# Signal_Generator_SCH.net
KiCad netlist of a schematic drawn in Altium Designer
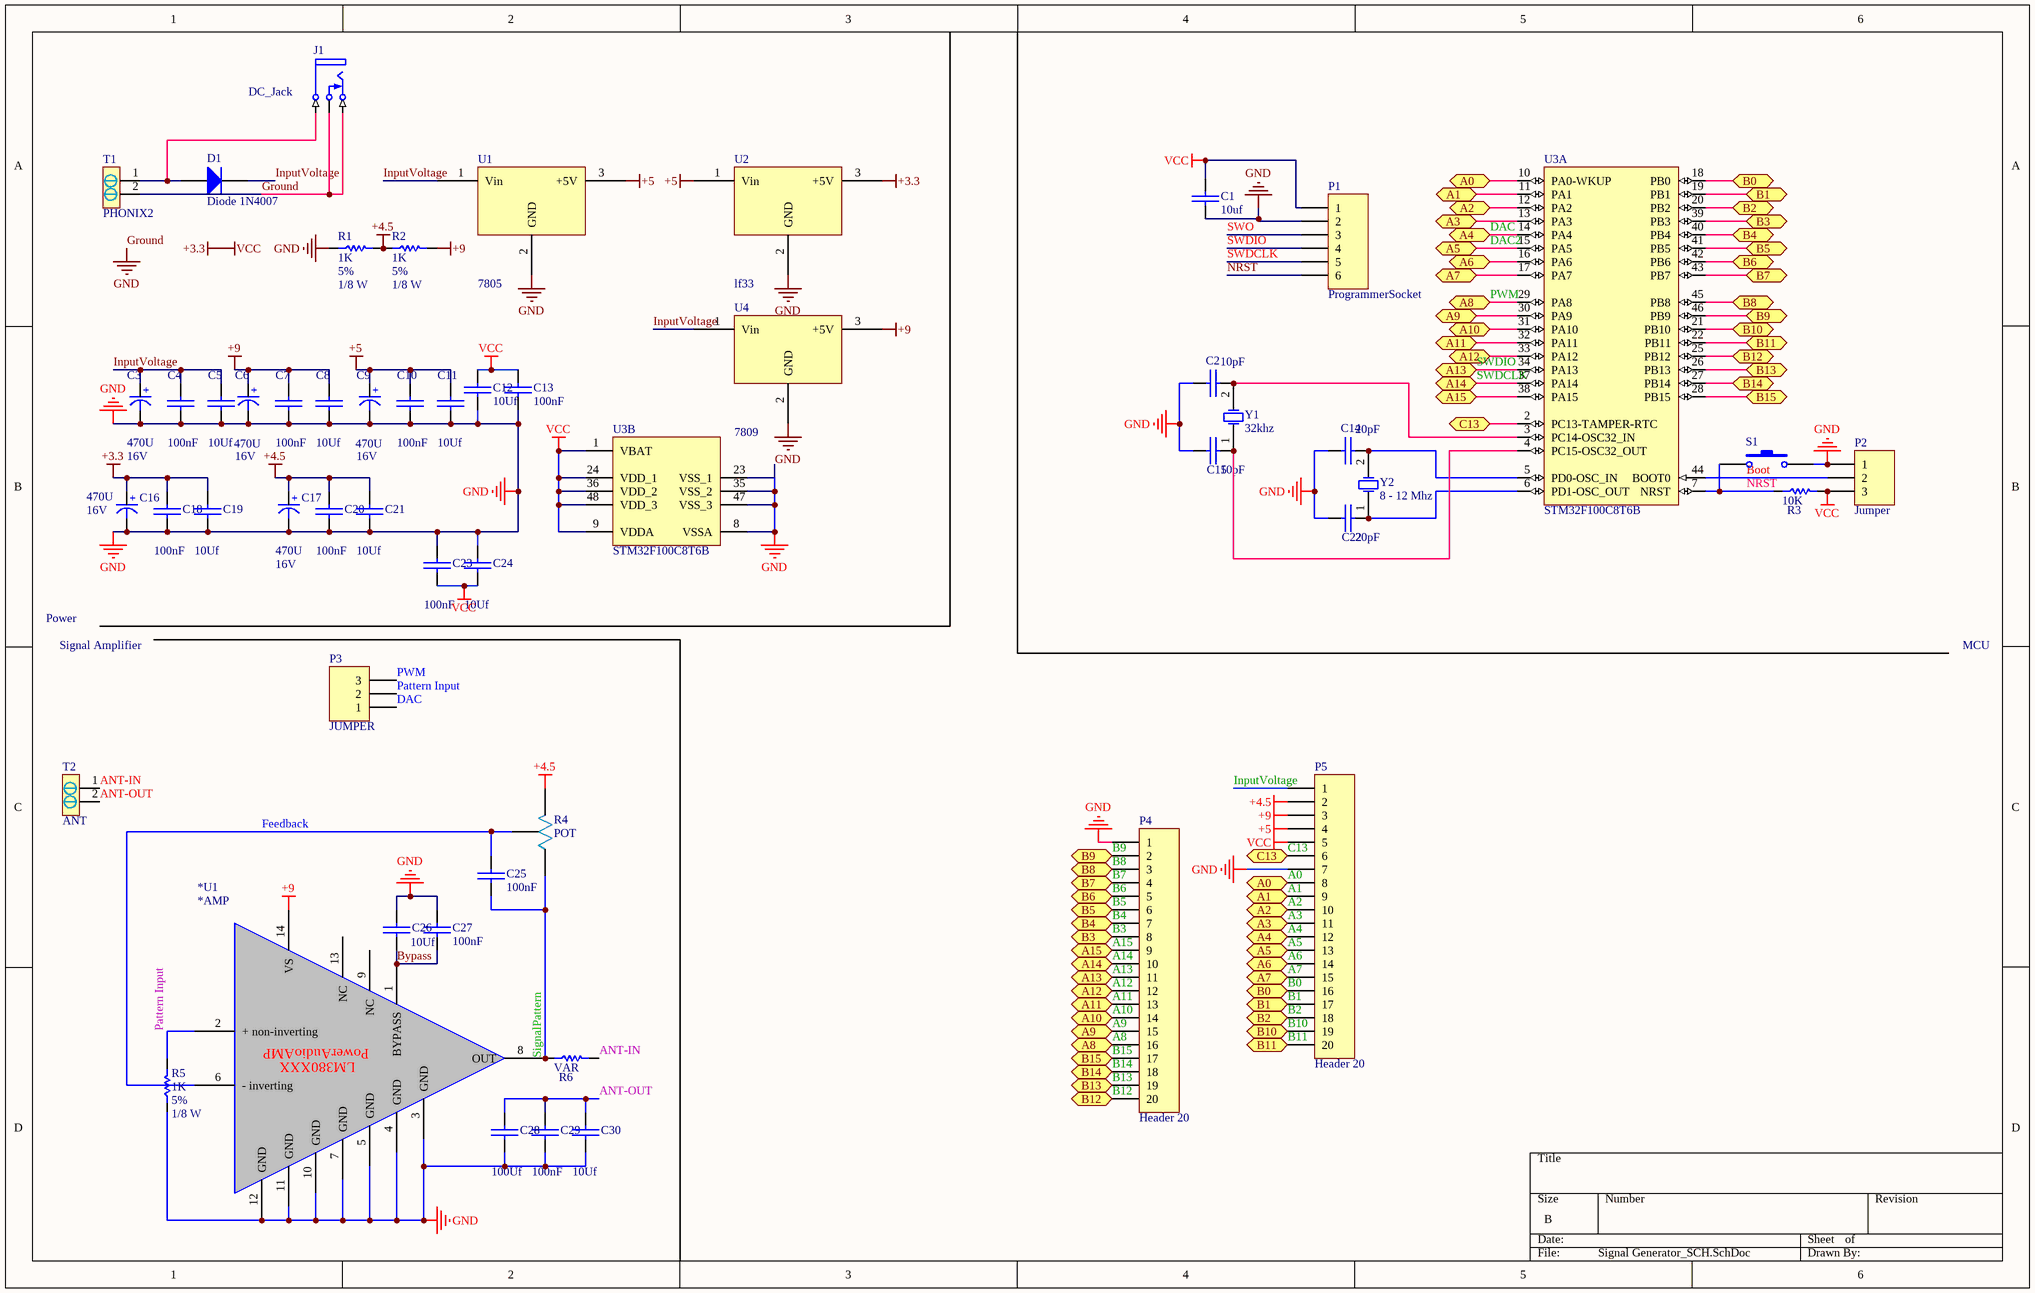
[diagram p0: Signal Generator_SCH.SchDoc]

(export (version "E")
  (design (tool "Eeschema 10.0.6"))
  (components
    (comp (ref "*U1")
      (value "*AMP")
      (footprint "LM380N-DIP")
      (fields (field (name "EMAIL") "Ehsan2754@yahoo.com"))
      (libsource (lib "Soga Library") (part "LM380N"))
    )
    (comp (ref "C1")
      (value "10uf")
      (footprint "SMD_CAP_1206")
      (description "Bipolar Capacitor")
      (fields (field (name "VOLTAGE") "100V") (field (name "DESIGNER") "Saeid Jorablo"))
      (libsource (lib "My Library") (part "Cap-Bipolar"))
    )
    (comp (ref "C2")
      (value "10pF")
      (footprint "SMD_CAP_1206")
      (description "Bipolar Capacitor")
      (fields (field (name "VOLTAGE") "100V") (field (name "DESIGNER") "Saeid Jorablo"))
      (libsource (lib "My Library") (part "Cap-Bipolar"))
    )
    (comp (ref "C3")
      (value "470U")
      (footprint "cap 01")
      (description "Polar Capacitor")
      (fields (field (name "VOLTAGE") "16V") (field (name "DESIGNER") "Saeid Jorablo"))
      (libsource (lib "My Library") (part "Cap-Polar"))
    )
    (comp (ref "C4")
      (value "100nF")
      (footprint "SMD_CAP_1206")
      (description "Bipolar Capacitor")
      (fields (field (name "VOLTAGE") "100V") (field (name "DESIGNER") "Saeid Jorablo"))
      (libsource (lib "My Library") (part "Cap-Bipolar"))
    )
    (comp (ref "C5")
      (value "10Uf")
      (footprint "SMD_CAP_1206")
      (description "Bipolar Capacitor")
      (fields (field (name "VOLTAGE") "100V") (field (name "DESIGNER") "Saeid Jorablo"))
      (libsource (lib "My Library") (part "Cap-Bipolar"))
    )
    (comp (ref "C6")
      (value "470U")
      (footprint "cap 01")
      (description "Polar Capacitor")
      (fields (field (name "VOLTAGE") "16V") (field (name "DESIGNER") "Saeid Jorablo"))
      (libsource (lib "My Library") (part "Cap-Polar"))
    )
    (comp (ref "C7")
      (value "100nF")
      (footprint "SMD_CAP_1206")
      (description "Bipolar Capacitor")
      (fields (field (name "VOLTAGE") "100V") (field (name "DESIGNER") "Saeid Jorablo"))
      (libsource (lib "My Library") (part "Cap-Bipolar"))
    )
    (comp (ref "C8")
      (value "10Uf")
      (footprint "SMD_CAP_1206")
      (description "Bipolar Capacitor")
      (fields (field (name "VOLTAGE") "100V") (field (name "DESIGNER") "Saeid Jorablo"))
      (libsource (lib "My Library") (part "Cap-Bipolar"))
    )
    (comp (ref "C9")
      (value "470U")
      (footprint "cap 01")
      (description "Polar Capacitor")
      (fields (field (name "VOLTAGE") "16V") (field (name "DESIGNER") "Saeid Jorablo"))
      (libsource (lib "My Library") (part "Cap-Polar"))
    )
    (comp (ref "C10")
      (value "100nF")
      (footprint "SMD_CAP_1206")
      (description "Bipolar Capacitor")
      (fields (field (name "VOLTAGE") "100V") (field (name "DESIGNER") "Saeid Jorablo"))
      (libsource (lib "My Library") (part "Cap-Bipolar"))
    )
    (comp (ref "C11")
      (value "10Uf")
      (footprint "SMD_CAP_1206")
      (description "Bipolar Capacitor")
      (fields (field (name "VOLTAGE") "100V") (field (name "DESIGNER") "Saeid Jorablo"))
      (libsource (lib "My Library") (part "Cap-Bipolar"))
    )
    (comp (ref "C12")
      (value "10Uf")
      (footprint "SMD_CAP_1206")
      (description "Bipolar Capacitor")
      (fields (field (name "VOLTAGE") "100V") (field (name "DESIGNER") "Saeid Jorablo"))
      (libsource (lib "My Library") (part "Cap-Bipolar"))
    )
    (comp (ref "C13")
      (value "100nF")
      (footprint "SMD_CAP_1206")
      (description "Bipolar Capacitor")
      (fields (field (name "VOLTAGE") "100V") (field (name "DESIGNER") "Saeid Jorablo"))
      (libsource (lib "My Library") (part "Cap-Bipolar"))
    )
    (comp (ref "C14")
      (value "20pF")
      (footprint "SMD_CAP_1206")
      (description "Bipolar Capacitor")
      (fields (field (name "VOLTAGE") "100V") (field (name "DESIGNER") "Saeid Jorablo"))
      (libsource (lib "My Library") (part "Cap-Bipolar"))
    )
    (comp (ref "C15")
      (value "10pF")
      (footprint "SMD_CAP_1206")
      (description "Bipolar Capacitor")
      (fields (field (name "VOLTAGE") "100V") (field (name "DESIGNER") "Saeid Jorablo"))
      (libsource (lib "My Library") (part "Cap-Bipolar"))
    )
    (comp (ref "C16")
      (value "470U")
      (footprint "cap 01")
      (description "Polar Capacitor")
      (fields (field (name "VOLTAGE") "16V") (field (name "DESIGNER") "Saeid Jorablo"))
      (libsource (lib "My Library") (part "Cap-Polar"))
    )
    (comp (ref "C17")
      (value "470U")
      (footprint "cap 01")
      (description "Polar Capacitor")
      (fields (field (name "VOLTAGE") "16V") (field (name "DESIGNER") "Saeid Jorablo"))
      (libsource (lib "My Library") (part "Cap-Polar"))
    )
    (comp (ref "C18")
      (value "100nF")
      (footprint "SMD_CAP_1206")
      (description "Bipolar Capacitor")
      (fields (field (name "VOLTAGE") "100V") (field (name "DESIGNER") "Saeid Jorablo"))
      (libsource (lib "My Library") (part "Cap-Bipolar"))
    )
    (comp (ref "C19")
      (value "10Uf")
      (footprint "SMD_CAP_1206")
      (description "Bipolar Capacitor")
      (fields (field (name "VOLTAGE") "100V") (field (name "DESIGNER") "Saeid Jorablo"))
      (libsource (lib "My Library") (part "Cap-Bipolar"))
    )
    (comp (ref "C20")
      (value "100nF")
      (footprint "SMD_CAP_1206")
      (description "Bipolar Capacitor")
      (fields (field (name "VOLTAGE") "100V") (field (name "DESIGNER") "Saeid Jorablo"))
      (libsource (lib "My Library") (part "Cap-Bipolar"))
    )
    (comp (ref "C21")
      (value "10Uf")
      (footprint "SMD_CAP_1206")
      (description "Bipolar Capacitor")
      (fields (field (name "VOLTAGE") "100V") (field (name "DESIGNER") "Saeid Jorablo"))
      (libsource (lib "My Library") (part "Cap-Bipolar"))
    )
    (comp (ref "C22")
      (value "20pF")
      (footprint "SMD_CAP_1206")
      (description "Bipolar Capacitor")
      (fields (field (name "VOLTAGE") "100V") (field (name "DESIGNER") "Saeid Jorablo"))
      (libsource (lib "My Library") (part "Cap-Bipolar"))
    )
    (comp (ref "C23")
      (value "100nF")
      (footprint "SMD_CAP_1206")
      (description "Bipolar Capacitor")
      (fields (field (name "VOLTAGE") "100V") (field (name "DESIGNER") "Saeid Jorablo"))
      (libsource (lib "My Library") (part "Cap-Bipolar"))
    )
    (comp (ref "C24")
      (value "10Uf")
      (footprint "SMD_CAP_1206")
      (description "Bipolar Capacitor")
      (fields (field (name "VOLTAGE") "100V") (field (name "DESIGNER") "Saeid Jorablo"))
      (libsource (lib "My Library") (part "Cap-Bipolar"))
    )
    (comp (ref "C25")
      (value "100nF")
      (footprint "SMD_CAP_1206")
      (description "Bipolar Capacitor")
      (fields (field (name "VOLTAGE") "100V") (field (name "DESIGNER") "Saeid Jorablo"))
      (libsource (lib "My Library") (part "Cap-Bipolar"))
    )
    (comp (ref "C26")
      (value "10Uf")
      (footprint "SMD_CAP_1206")
      (description "Bipolar Capacitor")
      (fields (field (name "VOLTAGE") "100V") (field (name "DESIGNER") "Saeid Jorablo"))
      (libsource (lib "My Library") (part "Cap-Bipolar"))
    )
    (comp (ref "C27")
      (value "100nF")
      (footprint "SMD_CAP_1206")
      (description "Bipolar Capacitor")
      (fields (field (name "VOLTAGE") "100V") (field (name "DESIGNER") "Saeid Jorablo"))
      (libsource (lib "My Library") (part "Cap-Bipolar"))
    )
    (comp (ref "C28")
      (value "100Uf")
      (footprint "SMD_CAP_1206")
      (description "Bipolar Capacitor")
      (fields (field (name "VOLTAGE") "100V") (field (name "DESIGNER") "Saeid Jorablo"))
      (libsource (lib "My Library") (part "Cap-Bipolar"))
    )
    (comp (ref "C29")
      (value "100nF")
      (footprint "SMD_CAP_1206")
      (description "Bipolar Capacitor")
      (fields (field (name "VOLTAGE") "100V") (field (name "DESIGNER") "Saeid Jorablo"))
      (libsource (lib "My Library") (part "Cap-Bipolar"))
    )
    (comp (ref "C30")
      (value "10Uf")
      (footprint "SMD_CAP_1206")
      (description "Bipolar Capacitor")
      (fields (field (name "VOLTAGE") "100V") (field (name "DESIGNER") "Saeid Jorablo"))
      (libsource (lib "My Library") (part "Cap-Bipolar"))
    )
    (comp (ref "D1")
      (value "Diode 1N4007")
      (footprint "DO-41")
      (description "1 Amp General Purpose Rectifier")
      (fields (field (name "PUBLISHER") "Altium Limited"))
      (libsource (lib "Miscellaneous Devices") (part "Diode 1N4007"))
    )
    (comp (ref "J1")
      (value "DC_Jack")
      (footprint "My_DC_Jack")
      (fields (field (name "PUBLISHER") "Altium Limited"))
      (libsource (lib "Mylib") (part "DC_Jack"))
    )
    (comp (ref "P1")
      (value "ProgrammerSocket")
      (footprint "HDR1X6")
      (description "Header, 6-Pin")
      (fields (field (name "PUBLISHER") "Altium Limited"))
      (libsource (lib "Miscellaneous Connectors") (part "Header 6"))
    )
    (comp (ref "P2")
      (value "Jumper")
      (footprint "HDR1X3")
      (description "Header, 3-Pin")
      (fields (field (name "PUBLISHER") "Altium Limited"))
      (libsource (lib "Miscellaneous Connectors") (part "Header 3"))
    )
    (comp (ref "P3")
      (value "JUMPER")
      (footprint "HDR1X3")
      (description "Header, 3-Pin")
      (fields (field (name "PUBLISHER") "Altium Limited"))
      (libsource (lib "") (part "Header 3_1"))
    )
    (comp (ref "P4")
      (value "Header 20")
      (footprint "HDR1X20")
      (description "Header, 20-Pin")
      (fields (field (name "PUBLISHER") "Altium Limited"))
      (libsource (lib "Miscellaneous Connectors") (part "Header 20"))
    )
    (comp (ref "P5")
      (value "Header 20")
      (footprint "HDR1X20")
      (description "Header, 20-Pin")
      (fields (field (name "PUBLISHER") "Altium Limited"))
      (libsource (lib "Miscellaneous Connectors") (part "Header 20"))
    )
    (comp (ref "R1")
      (value "1K")
      (footprint "RES 1206 (3216X08L)")
      (description "Resistor")
      (fields (field (name "TOLERANCE") "5%") (field (name "POWER") "1/8 W"))
      (libsource (lib "My Library") (part "Resistor"))
    )
    (comp (ref "R2")
      (value "1K")
      (footprint "RES 1206 (3216X08L)")
      (description "Resistor")
      (fields (field (name "TOLERANCE") "5%") (field (name "POWER") "1/8 W"))
      (libsource (lib "My Library") (part "Resistor"))
    )
    (comp (ref "R3")
      (value "10K")
      (footprint "RES 1206 (3216X08L)")
      (description "Resistor")
      (fields (field (name "TOLERANCE") "5%") (field (name "POWER") "1/8 W"))
      (libsource (lib "My Library") (part "Resistor"))
    )
    (comp (ref "R4") (value "POT") (footprint "MOL_1") (libsource (lib "My_lib_new") (part "POT")))
    (comp (ref "R5")
      (value "1K")
      (footprint "RES 1206 (3216X08L)")
      (description "Resistor")
      (fields (field (name "TOLERANCE") "5%") (field (name "POWER") "1/8 W"))
      (libsource (lib "My Library") (part "Resistor"))
    )
    (comp (ref "R6")
      (value "VAR")
      (footprint "RES 1206 (3216X08L)")
      (description "Resistor")
      (fields (field (name "TOLERANCE") "5%") (field (name "POWER") "1/8 W"))
      (libsource (lib "My Library") (part "Resistor"))
    )
    (comp (ref "S1")
      (value "Switch PB")
      (footprint "Switch - Push to On")
      (description "Push Button Switch")
      (libsource (lib "My Library") (part "Switch PB"))
    )
    (comp (ref "T1") (value "PHONIX2") (footprint "PHONIX2") (libsource (lib "My_lib_new") (part "PHONIX2")))
    (comp (ref "T2") (value "ANT") (footprint "PHONIX2") (libsource (lib "My_lib_new") (part "PHONIX2")))
    (comp (ref "U1")
      (value "7805")
      (footprint "My_TO-220")
      (description "Regulator")
      (libsource (lib "Mylib") (part "7805"))
    )
    (comp (ref "U2")
      (value "lf33")
      (footprint "My_TO-220")
      (description "Regulator")
      (libsource (lib "Mylib") (part "7805"))
    )
    (comp (ref "U3")
      (value "STM32F100C8T6B")
      (footprint "STM-LQFP48_N")
      (libsource (lib "ST Microelectronics STM32 F1") (part "STM32F100C8T6B"))
    )
    (comp (ref "U4")
      (value "7809")
      (footprint "My_TO-220")
      (description "Regulator")
      (libsource (lib "Mylib") (part "7805"))
    )
    (comp (ref "Y1")
      (value "32khz")
      (footprint "XTAL RTC")
      (description "XTAL Crystal")
      (libsource (lib "My Library") (part "XTAL"))
    )
    (comp (ref "Y2")
      (value "8 - 12 Mhz")
      (footprint "XTAL Small")
      (description "XTAL Crystal")
      (libsource (lib "My Library") (part "XTAL"))
    )
  )
  (nets
    (net (code "1") (name "+3.3") (class "Default")
      (node (ref "C1") (pin "2") (pinfunction "-_2") (pintype "passive"))
      (node (ref "C12") (pin "2") (pinfunction "-_2") (pintype "passive"))
      (node (ref "C13") (pin "2") (pinfunction "-_2") (pintype "passive"))
      (node (ref "C16") (pin "1") (pinfunction "+_1") (pintype "passive"))
      (node (ref "C18") (pin "1") (pinfunction "+_1") (pintype "passive"))
      (node (ref "C19") (pin "1") (pinfunction "+_1") (pintype "passive"))
      (node (ref "C23") (pin "2") (pinfunction "-_2") (pintype "passive"))
      (node (ref "C24") (pin "2") (pinfunction "-_2") (pintype "passive"))
      (node (ref "P1") (pin "1") (pinfunction "1_1") (pintype "passive"))
      (node (ref "P2") (pin "3") (pinfunction "3_3") (pintype "passive"))
      (node (ref "P5") (pin "5") (pinfunction "5_5") (pintype "passive"))
      (node (ref "R3") (pin "2") (pinfunction "2_2") (pintype "passive"))
      (node (ref "U2") (pin "3") (pinfunction "+5V_3") (pintype "power_in"))
      (node (ref "U3") (pin "1") (pinfunction "VBAT_1") (pintype "power_in"))
      (node (ref "U3") (pin "24") (pinfunction "VDD_1_24") (pintype "power_in"))
      (node (ref "U3") (pin "36") (pinfunction "VDD_2_36") (pintype "power_in"))
      (node (ref "U3") (pin "48") (pinfunction "VDD_3_48") (pintype "power_in"))
      (node (ref "U3") (pin "9") (pinfunction "VDDA_9") (pintype "power_in"))
    )
    (net (code "2") (name "+4.5") (class "Default")
      (node (ref "C17") (pin "1") (pinfunction "+_1") (pintype "passive"))
      (node (ref "C20") (pin "1") (pinfunction "+_1") (pintype "passive"))
      (node (ref "C21") (pin "1") (pinfunction "+_1") (pintype "passive"))
      (node (ref "P5") (pin "2") (pinfunction "2_2") (pintype "passive"))
      (node (ref "R1") (pin "2") (pinfunction "2_2") (pintype "passive"))
      (node (ref "R2") (pin "1") (pinfunction "1_1") (pintype "passive"))
      (node (ref "R4") (pin "3") (pintype "passive"))
    )
    (net (code "3") (name "+5") (class "Default")
      (node (ref "C10") (pin "1") (pinfunction "+_1") (pintype "passive"))
      (node (ref "C11") (pin "1") (pinfunction "+_1") (pintype "passive"))
      (node (ref "C9") (pin "1") (pinfunction "+_1") (pintype "passive"))
      (node (ref "P5") (pin "4") (pinfunction "4_4") (pintype "passive"))
      (node (ref "U1") (pin "3") (pinfunction "+5V_3") (pintype "power_in"))
      (node (ref "U2") (pin "1") (pinfunction "Vin_1") (pintype "power_in"))
    )
    (net (code "4") (name "+9") (class "Default")
      (node (ref "*U1") (pin "14") (pinfunction "VS_14") (pintype "passive"))
      (node (ref "C6") (pin "1") (pinfunction "+_1") (pintype "passive"))
      (node (ref "C7") (pin "1") (pinfunction "+_1") (pintype "passive"))
      (node (ref "C8") (pin "1") (pinfunction "+_1") (pintype "passive"))
      (node (ref "P5") (pin "3") (pinfunction "3_3") (pintype "passive"))
      (node (ref "R2") (pin "2") (pinfunction "2_2") (pintype "passive"))
      (node (ref "U4") (pin "3") (pinfunction "+5V_3") (pintype "power_in"))
    )
    (net (code "5") (name "/A0") (class "Default")
      (node (ref "P5") (pin "8") (pinfunction "8_8") (pintype "passive"))
      (node (ref "U3") (pin "10") (pinfunction "PA0-WKUP_10") (pintype "bidirectional"))
    )
    (net (code "6") (name "/A1") (class "Default")
      (node (ref "P5") (pin "9") (pinfunction "9_9") (pintype "passive"))
      (node (ref "U3") (pin "11") (pinfunction "PA1_11") (pintype "bidirectional"))
    )
    (net (code "7") (name "/A2") (class "Default")
      (node (ref "P5") (pin "10") (pinfunction "10_10") (pintype "passive"))
      (node (ref "U3") (pin "12") (pinfunction "PA2_12") (pintype "bidirectional"))
    )
    (net (code "8") (name "/A3") (class "Default")
      (node (ref "P5") (pin "11") (pinfunction "11_11") (pintype "passive"))
      (node (ref "U3") (pin "13") (pinfunction "PA3_13") (pintype "bidirectional"))
    )
    (net (code "9") (name "/A4") (class "Default")
      (node (ref "P3") (pin "1") (pinfunction "1_1") (pintype "passive"))
      (node (ref "P5") (pin "12") (pinfunction "12_12") (pintype "passive"))
      (node (ref "U3") (pin "14") (pinfunction "PA4_14") (pintype "bidirectional"))
    )
    (net (code "10") (name "/A5") (class "Default")
      (node (ref "P5") (pin "13") (pinfunction "13_13") (pintype "passive"))
      (node (ref "U3") (pin "15") (pinfunction "PA5_15") (pintype "bidirectional"))
    )
    (net (code "11") (name "/A6") (class "Default")
      (node (ref "P5") (pin "14") (pinfunction "14_14") (pintype "passive"))
      (node (ref "U3") (pin "16") (pinfunction "PA6_16") (pintype "bidirectional"))
    )
    (net (code "12") (name "/A7") (class "Default")
      (node (ref "P5") (pin "15") (pinfunction "15_15") (pintype "passive"))
      (node (ref "U3") (pin "17") (pinfunction "PA7_17") (pintype "bidirectional"))
    )
    (net (code "13") (name "/A8") (class "Default")
      (node (ref "P3") (pin "3") (pinfunction "3_3") (pintype "passive"))
      (node (ref "P4") (pin "16") (pinfunction "16_16") (pintype "passive"))
      (node (ref "U3") (pin "29") (pinfunction "PA8_29") (pintype "bidirectional"))
    )
    (net (code "14") (name "/A9") (class "Default")
      (node (ref "P4") (pin "15") (pinfunction "15_15") (pintype "passive"))
      (node (ref "U3") (pin "30") (pinfunction "PA9_30") (pintype "bidirectional"))
    )
    (net (code "15") (name "/A10") (class "Default")
      (node (ref "P4") (pin "14") (pinfunction "14_14") (pintype "passive"))
      (node (ref "U3") (pin "31") (pinfunction "PA10_31") (pintype "bidirectional"))
    )
    (net (code "16") (name "/A11") (class "Default")
      (node (ref "P4") (pin "13") (pinfunction "13_13") (pintype "passive"))
      (node (ref "U3") (pin "32") (pinfunction "PA11_32") (pintype "bidirectional"))
    )
    (net (code "17") (name "/A12") (class "Default")
      (node (ref "P4") (pin "12") (pinfunction "12_12") (pintype "passive"))
      (node (ref "U3") (pin "33") (pinfunction "PA12_33") (pintype "bidirectional"))
    )
    (net (code "18") (name "/A13") (class "Default")
      (node (ref "P1") (pin "4") (pinfunction "4_4") (pintype "passive"))
      (node (ref "P4") (pin "11") (pinfunction "11_11") (pintype "passive"))
      (node (ref "U3") (pin "34") (pinfunction "PA13_34") (pintype "bidirectional"))
    )
    (net (code "19") (name "/A14") (class "Default")
      (node (ref "P1") (pin "5") (pinfunction "5_5") (pintype "passive"))
      (node (ref "P4") (pin "10") (pinfunction "10_10") (pintype "passive"))
      (node (ref "U3") (pin "37") (pinfunction "PA14_37") (pintype "bidirectional"))
    )
    (net (code "20") (name "/A15") (class "Default")
      (node (ref "P4") (pin "9") (pinfunction "9_9") (pintype "passive"))
      (node (ref "U3") (pin "38") (pinfunction "PA15_38") (pintype "bidirectional"))
    )
    (net (code "21") (name "/ANT-IN") (class "Default")
      (node (ref "R6") (pin "2") (pinfunction "2_2") (pintype "passive"))
      (node (ref "T2") (pin "1") (pintype "passive"))
    )
    (net (code "22") (name "/ANT-OUT") (class "Default")
      (node (ref "C28") (pin "1") (pinfunction "+_1") (pintype "passive"))
      (node (ref "C29") (pin "1") (pinfunction "+_1") (pintype "passive"))
      (node (ref "C30") (pin "1") (pinfunction "+_1") (pintype "passive"))
      (node (ref "T2") (pin "2") (pintype "passive"))
    )
    (net (code "23") (name "/B0") (class "Default")
      (node (ref "P5") (pin "16") (pinfunction "16_16") (pintype "passive"))
      (node (ref "U3") (pin "18") (pinfunction "PB0_18") (pintype "bidirectional"))
    )
    (net (code "24") (name "/B1") (class "Default")
      (node (ref "P5") (pin "17") (pinfunction "17_17") (pintype "passive"))
      (node (ref "U3") (pin "19") (pinfunction "PB1_19") (pintype "bidirectional"))
    )
    (net (code "25") (name "/B2") (class "Default")
      (node (ref "P5") (pin "18") (pinfunction "18_18") (pintype "passive"))
      (node (ref "U3") (pin "20") (pinfunction "PB2_20") (pintype "bidirectional"))
    )
    (net (code "26") (name "/B3") (class "Default")
      (node (ref "P4") (pin "8") (pinfunction "8_8") (pintype "passive"))
      (node (ref "U3") (pin "39") (pinfunction "PB3_39") (pintype "bidirectional"))
    )
    (net (code "27") (name "/B4") (class "Default")
      (node (ref "P4") (pin "7") (pinfunction "7_7") (pintype "passive"))
      (node (ref "U3") (pin "40") (pinfunction "PB4_40") (pintype "bidirectional"))
    )
    (net (code "28") (name "/B5") (class "Default")
      (node (ref "P4") (pin "6") (pinfunction "6_6") (pintype "passive"))
      (node (ref "U3") (pin "41") (pinfunction "PB5_41") (pintype "bidirectional"))
    )
    (net (code "29") (name "/B6") (class "Default")
      (node (ref "P4") (pin "5") (pinfunction "5_5") (pintype "passive"))
      (node (ref "U3") (pin "42") (pinfunction "PB6_42") (pintype "bidirectional"))
    )
    (net (code "30") (name "/B7") (class "Default")
      (node (ref "P4") (pin "4") (pinfunction "4_4") (pintype "passive"))
      (node (ref "U3") (pin "43") (pinfunction "PB7_43") (pintype "bidirectional"))
    )
    (net (code "31") (name "/B8") (class "Default")
      (node (ref "P4") (pin "3") (pinfunction "3_3") (pintype "passive"))
      (node (ref "U3") (pin "45") (pinfunction "PB8_45") (pintype "bidirectional"))
    )
    (net (code "32") (name "/B9") (class "Default")
      (node (ref "P4") (pin "2") (pinfunction "2_2") (pintype "passive"))
      (node (ref "U3") (pin "46") (pinfunction "PB9_46") (pintype "bidirectional"))
    )
    (net (code "33") (name "/B10") (class "Default")
      (node (ref "P5") (pin "19") (pinfunction "19_19") (pintype "passive"))
      (node (ref "U3") (pin "21") (pinfunction "PB10_21") (pintype "bidirectional"))
    )
    (net (code "34") (name "/B11") (class "Default")
      (node (ref "P5") (pin "20") (pinfunction "20_20") (pintype "passive"))
      (node (ref "U3") (pin "22") (pinfunction "PB11_22") (pintype "bidirectional"))
    )
    (net (code "35") (name "/B12") (class "Default")
      (node (ref "P4") (pin "20") (pinfunction "20_20") (pintype "passive"))
      (node (ref "U3") (pin "25") (pinfunction "PB12_25") (pintype "bidirectional"))
    )
    (net (code "36") (name "/B13") (class "Default")
      (node (ref "P4") (pin "19") (pinfunction "19_19") (pintype "passive"))
      (node (ref "U3") (pin "26") (pinfunction "PB13_26") (pintype "bidirectional"))
    )
    (net (code "37") (name "/B14") (class "Default")
      (node (ref "P4") (pin "18") (pinfunction "18_18") (pintype "passive"))
      (node (ref "U3") (pin "27") (pinfunction "PB14_27") (pintype "bidirectional"))
    )
    (net (code "38") (name "/B15") (class "Default")
      (node (ref "P4") (pin "17") (pinfunction "17_17") (pintype "passive"))
      (node (ref "U3") (pin "28") (pinfunction "PB15_28") (pintype "bidirectional"))
    )
    (net (code "39") (name "/Boot") (class "Default")
      (node (ref "P2") (pin "2") (pinfunction "2_2") (pintype "passive"))
      (node (ref "U3") (pin "44") (pinfunction "BOOT0_44") (pintype "input"))
    )
    (net (code "40") (name "/Bypass") (class "Default")
      (node (ref "*U1") (pin "1") (pinfunction "BYPASS_1") (pintype "passive"))
      (node (ref "C26") (pin "1") (pinfunction "+_1") (pintype "passive"))
      (node (ref "C27") (pin "1") (pinfunction "+_1") (pintype "passive"))
    )
    (net (code "41") (name "/C13") (class "Default")
      (node (ref "P5") (pin "6") (pinfunction "6_6") (pintype "passive"))
      (node (ref "U3") (pin "2") (pinfunction "PC13-TAMPER-RTC_2") (pintype "bidirectional"))
    )
    (net (code "42") (name "/Feedback") (class "Default")
      (node (ref "*U1") (pin "6") (pinfunction "-_inverting_6") (pintype "passive"))
      (node (ref "C25") (pin "1") (pinfunction "+_1") (pintype "passive"))
      (node (ref "R4") (pin "2") (pintype "passive"))
    )
    (net (code "43") (name "/InputVoltage") (class "Default")
      (node (ref "C3") (pin "1") (pinfunction "+_1") (pintype "passive"))
      (node (ref "C4") (pin "1") (pinfunction "+_1") (pintype "passive"))
      (node (ref "C5") (pin "1") (pinfunction "+_1") (pintype "passive"))
      (node (ref "D1") (pin "2") (pinfunction "K_2") (pintype "passive"))
      (node (ref "P5") (pin "1") (pinfunction "1_1") (pintype "passive"))
      (node (ref "U1") (pin "1") (pinfunction "Vin_1") (pintype "power_in"))
      (node (ref "U4") (pin "1") (pinfunction "Vin_1") (pintype "power_in"))
    )
    (net (code "44") (name "/NRST") (class "Default")
      (node (ref "P1") (pin "6") (pinfunction "6_6") (pintype "passive"))
      (node (ref "R3") (pin "1") (pinfunction "1_1") (pintype "passive"))
      (node (ref "S1") (pin "1") (pinfunction "1_1") (pintype "passive"))
      (node (ref "U3") (pin "7") (pinfunction "NRST_7") (pintype "bidirectional"))
    )
    (net (code "45") (name "/Pattern Input") (class "Default")
      (node (ref "*U1") (pin "2") (pinfunction "+_non-inverting_2") (pintype "passive"))
      (node (ref "P3") (pin "2") (pinfunction "2_2") (pintype "passive"))
      (node (ref "R5") (pin "2") (pinfunction "2_2") (pintype "passive"))
    )
    (net (code "46") (name "/SWO") (class "Default")
      (node (ref "P1") (pin "3") (pinfunction "3_3") (pintype "passive"))
    )
    (net (code "47") (name "/SignalPattern") (class "Default")
      (node (ref "*U1") (pin "8") (pinfunction "OUT_8") (pintype "passive"))
      (node (ref "C25") (pin "2") (pinfunction "-_2") (pintype "passive"))
      (node (ref "R4") (pin "1") (pintype "passive"))
      (node (ref "R6") (pin "1") (pinfunction "1_1") (pintype "passive"))
    )
    (net (code "48") (name "GND") (class "Default")
      (node (ref "*U1") (pin "10") (pinfunction "GND_10") (pintype "passive"))
      (node (ref "*U1") (pin "11") (pinfunction "GND_11") (pintype "passive"))
      (node (ref "*U1") (pin "12") (pinfunction "GND_12") (pintype "passive"))
      (node (ref "*U1") (pin "3") (pinfunction "GND_3") (pintype "passive"))
      (node (ref "*U1") (pin "4") (pinfunction "GND_4") (pintype "passive"))
      (node (ref "*U1") (pin "5") (pinfunction "GND_5") (pintype "passive"))
      (node (ref "*U1") (pin "7") (pinfunction "GND_7") (pintype "passive"))
      (node (ref "C1") (pin "1") (pinfunction "+_1") (pintype "passive"))
      (node (ref "C10") (pin "2") (pinfunction "-_2") (pintype "passive"))
      (node (ref "C11") (pin "2") (pinfunction "-_2") (pintype "passive"))
      (node (ref "C12") (pin "1") (pinfunction "+_1") (pintype "passive"))
      (node (ref "C13") (pin "1") (pinfunction "+_1") (pintype "passive"))
      (node (ref "C14") (pin "2") (pinfunction "-_2") (pintype "passive"))
      (node (ref "C15") (pin "2") (pinfunction "-_2") (pintype "passive"))
      (node (ref "C16") (pin "2") (pinfunction "-_2") (pintype "passive"))
      (node (ref "C17") (pin "2") (pinfunction "-_2") (pintype "passive"))
      (node (ref "C18") (pin "2") (pinfunction "-_2") (pintype "passive"))
      (node (ref "C19") (pin "2") (pinfunction "-_2") (pintype "passive"))
      (node (ref "C2") (pin "2") (pinfunction "-_2") (pintype "passive"))
      (node (ref "C20") (pin "2") (pinfunction "-_2") (pintype "passive"))
      (node (ref "C21") (pin "2") (pinfunction "-_2") (pintype "passive"))
      (node (ref "C22") (pin "2") (pinfunction "-_2") (pintype "passive"))
      (node (ref "C23") (pin "1") (pinfunction "+_1") (pintype "passive"))
      (node (ref "C24") (pin "1") (pinfunction "+_1") (pintype "passive"))
      (node (ref "C26") (pin "2") (pinfunction "-_2") (pintype "passive"))
      (node (ref "C27") (pin "2") (pinfunction "-_2") (pintype "passive"))
      (node (ref "C28") (pin "2") (pinfunction "-_2") (pintype "passive"))
      (node (ref "C29") (pin "2") (pinfunction "-_2") (pintype "passive"))
      (node (ref "C3") (pin "2") (pinfunction "-_2") (pintype "passive"))
      (node (ref "C30") (pin "2") (pinfunction "-_2") (pintype "passive"))
      (node (ref "C4") (pin "2") (pinfunction "-_2") (pintype "passive"))
      (node (ref "C5") (pin "2") (pinfunction "-_2") (pintype "passive"))
      (node (ref "C6") (pin "2") (pinfunction "-_2") (pintype "passive"))
      (node (ref "C7") (pin "2") (pinfunction "-_2") (pintype "passive"))
      (node (ref "C8") (pin "2") (pinfunction "-_2") (pintype "passive"))
      (node (ref "C9") (pin "2") (pinfunction "-_2") (pintype "passive"))
      (node (ref "J1") (pin "1") (pinfunction "T_1") (pintype "input"))
      (node (ref "J1") (pin "2") (pinfunction "TN_2") (pintype "passive"))
      (node (ref "P1") (pin "2") (pinfunction "2_2") (pintype "passive"))
      (node (ref "P2") (pin "1") (pinfunction "1_1") (pintype "passive"))
      (node (ref "P4") (pin "1") (pinfunction "1_1") (pintype "passive"))
      (node (ref "P5") (pin "7") (pinfunction "7_7") (pintype "passive"))
      (node (ref "R1") (pin "1") (pinfunction "1_1") (pintype "passive"))
      (node (ref "R5") (pin "1") (pinfunction "1_1") (pintype "passive"))
      (node (ref "S1") (pin "2") (pinfunction "2_2") (pintype "passive"))
      (node (ref "T1") (pin "2") (pintype "passive"))
      (node (ref "U1") (pin "2") (pinfunction "GND_2") (pintype "power_in"))
      (node (ref "U2") (pin "2") (pinfunction "GND_2") (pintype "power_in"))
      (node (ref "U3") (pin "23") (pinfunction "VSS_1_23") (pintype "power_in"))
      (node (ref "U3") (pin "35") (pinfunction "VSS_2_35") (pintype "power_in"))
      (node (ref "U3") (pin "47") (pinfunction "VSS_3_47") (pintype "power_in"))
      (node (ref "U3") (pin "8") (pinfunction "VSSA_8") (pintype "power_in"))
      (node (ref "U4") (pin "2") (pinfunction "GND_2") (pintype "power_in"))
    )
    (net (code "49") (name "Net-(C2-+)") (class "Default")
      (node (ref "C2") (pin "1") (pinfunction "+_1") (pintype "passive"))
      (node (ref "U3") (pin "3") (pinfunction "PC14-OSC32_IN_3") (pintype "bidirectional"))
      (node (ref "Y1") (pin "2") (pinfunction "OSC2_2") (pintype "passive"))
    )
    (net (code "50") (name "Net-(C14-+)") (class "Default")
      (node (ref "C14") (pin "1") (pinfunction "+_1") (pintype "passive"))
      (node (ref "U3") (pin "5") (pinfunction "PD0-OSC_IN_5") (pintype "bidirectional"))
      (node (ref "Y2") (pin "2") (pinfunction "OSC2_2") (pintype "passive"))
    )
    (net (code "51") (name "Net-(C15-+)") (class "Default")
      (node (ref "C15") (pin "1") (pinfunction "+_1") (pintype "passive"))
      (node (ref "U3") (pin "4") (pinfunction "PC15-OSC32_OUT_4") (pintype "bidirectional"))
      (node (ref "Y1") (pin "1") (pinfunction "OSC1_1") (pintype "passive"))
    )
    (net (code "52") (name "Net-(C22-+)") (class "Default")
      (node (ref "C22") (pin "1") (pinfunction "+_1") (pintype "passive"))
      (node (ref "U3") (pin "6") (pinfunction "PD1-OSC_OUT_6") (pintype "bidirectional"))
      (node (ref "Y2") (pin "1") (pinfunction "OSC1_1") (pintype "passive"))
    )
    (net (code "53") (name "Net-(D1-A)") (class "Default")
      (node (ref "D1") (pin "1") (pinfunction "A_1") (pintype "passive"))
      (node (ref "J1") (pin "3") (pinfunction "S_3") (pintype "input"))
      (node (ref "T1") (pin "1") (pintype "passive"))
    )
    (net (code "54") (name "unconnected-(*U1-NC-Pad9)") (class "Default")
      (node (ref "*U1") (pin "9") (pinfunction "NC_9") (pintype "passive"))
    )
    (net (code "55") (name "unconnected-(*U1-NC-Pad13)") (class "Default")
      (node (ref "*U1") (pin "13") (pinfunction "NC_13") (pintype "passive"))
    )
  )
)
